# hybrid_lower_pcb3_3.net
KiCad netlist of a schematic drawn in EAGLE
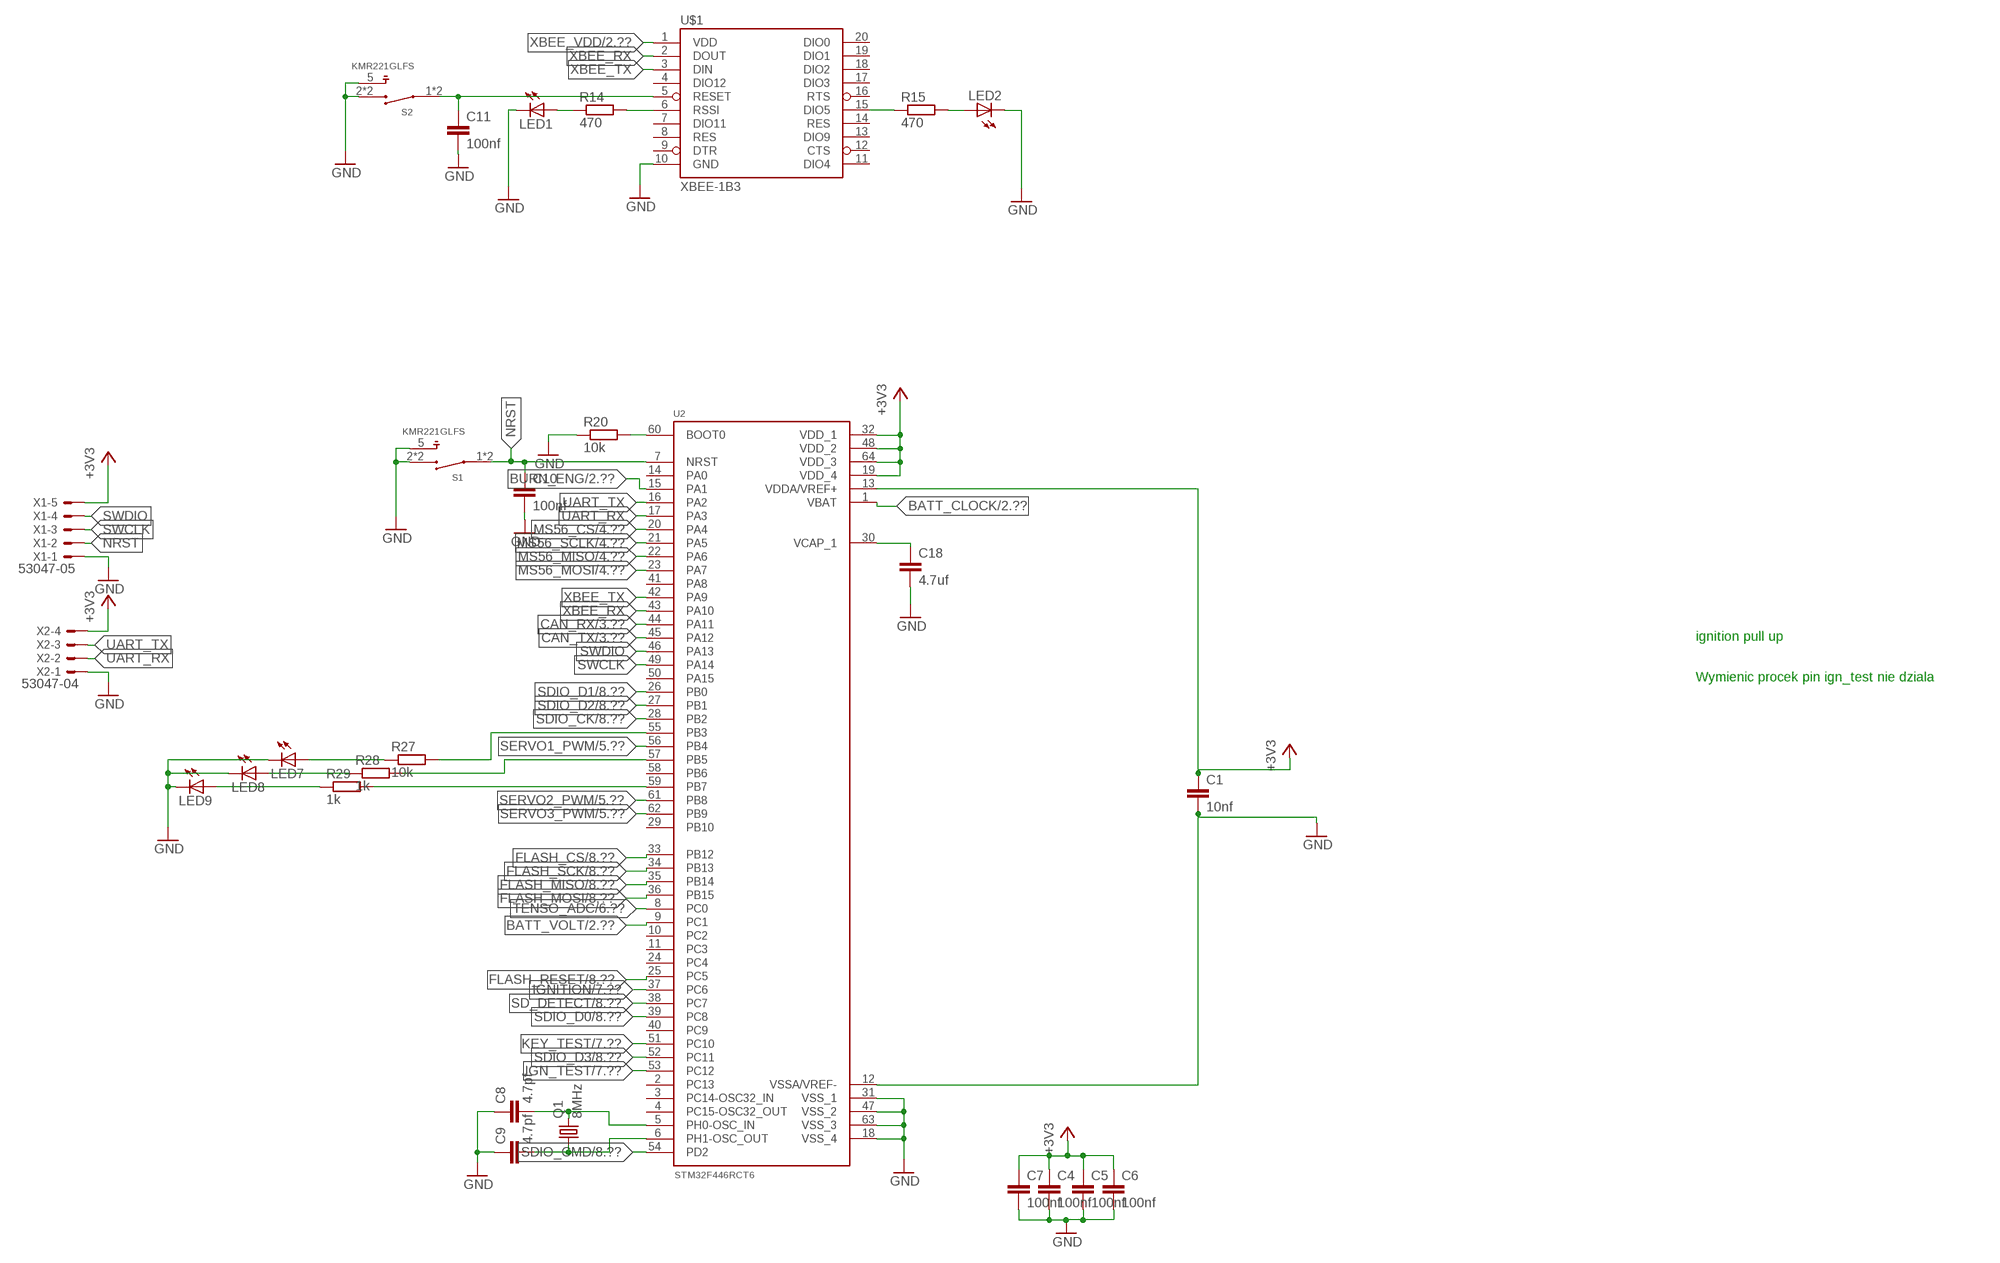
[diagram p0: schematic, sheet 1]
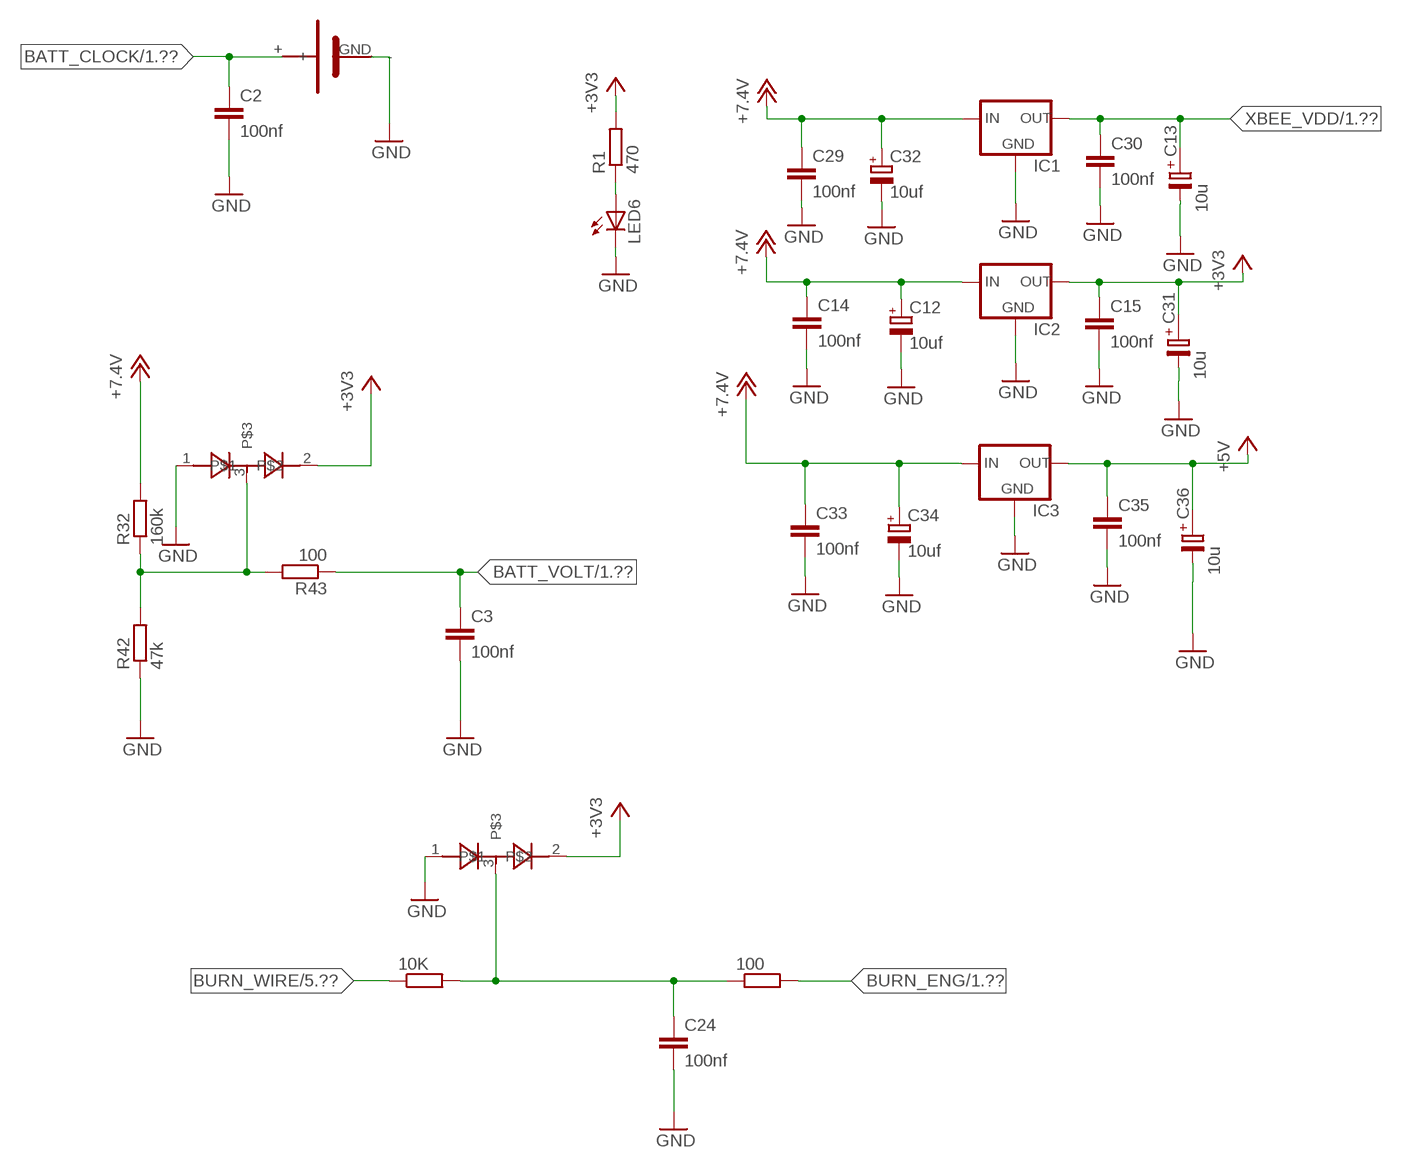
[diagram p1: schematic, sheet 2]
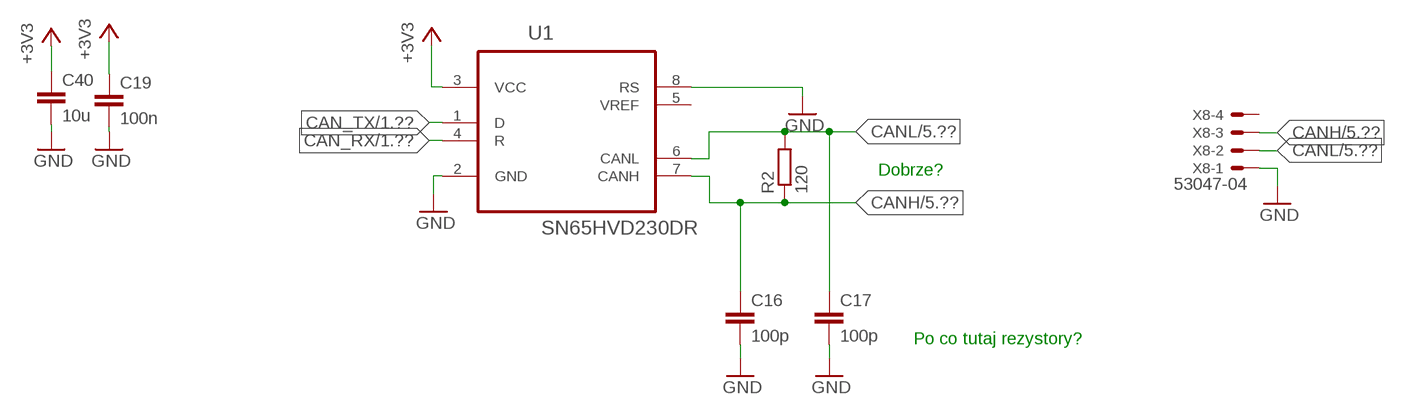
[diagram p2: schematic, sheet 3]
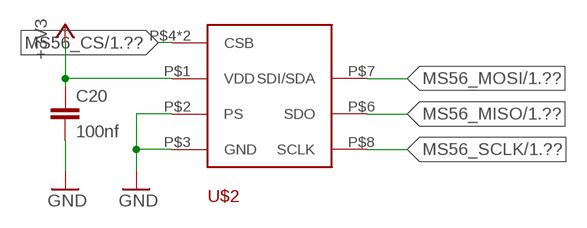
[diagram p3: schematic, sheet 4]
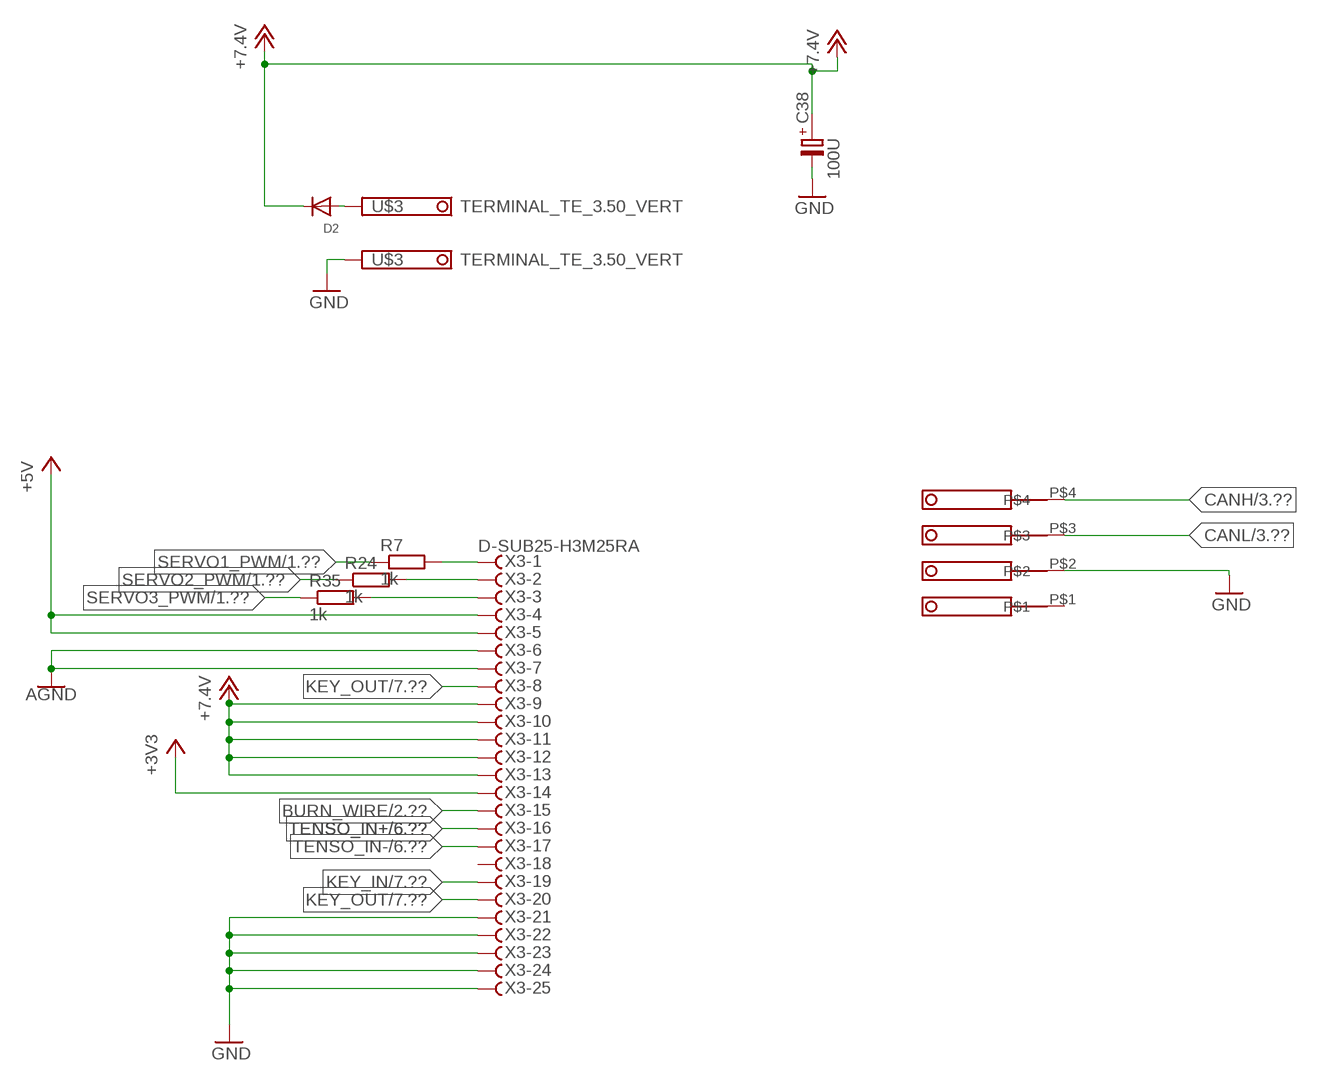
[diagram p4: schematic, sheet 5]
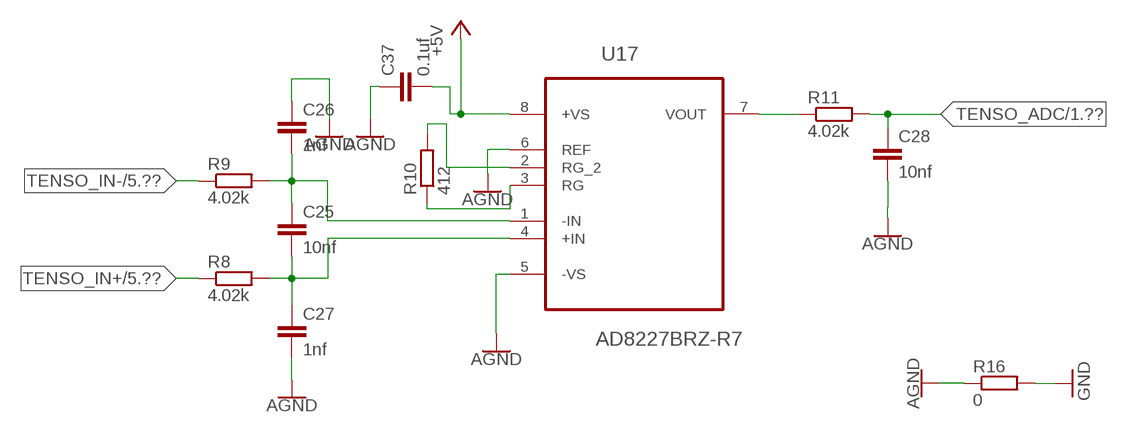
[diagram p5: schematic, sheet 6]
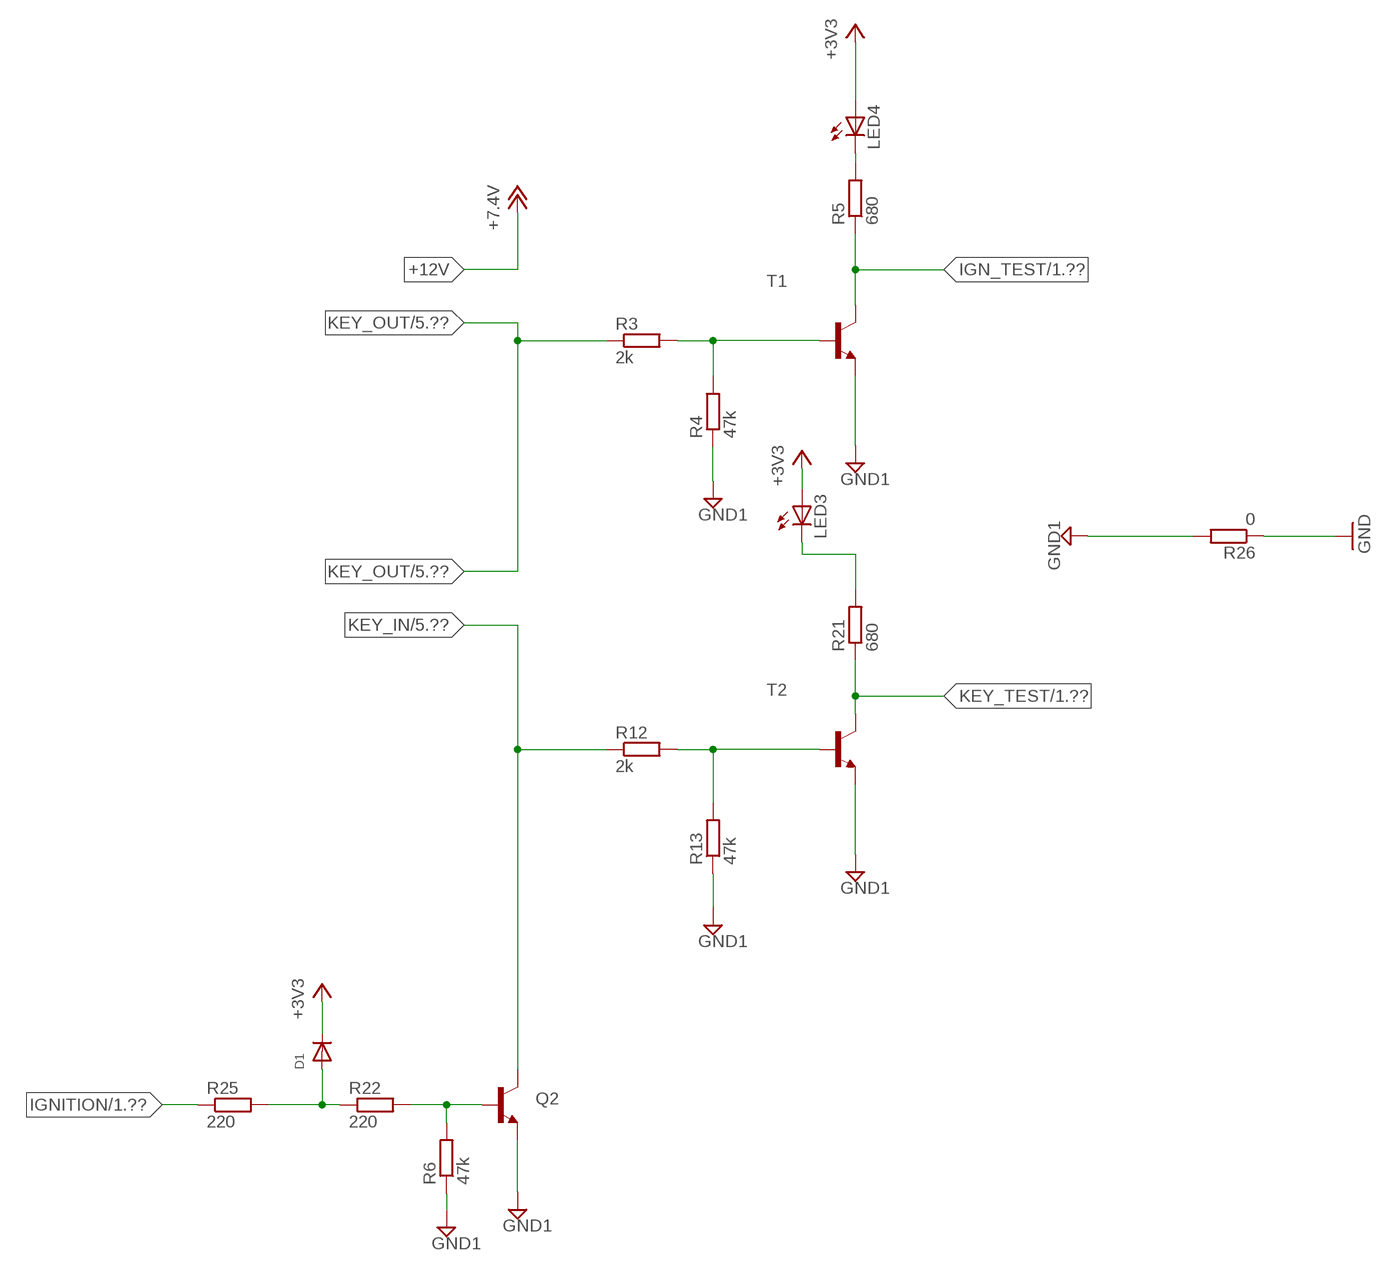
[diagram p6: schematic, sheet 7]
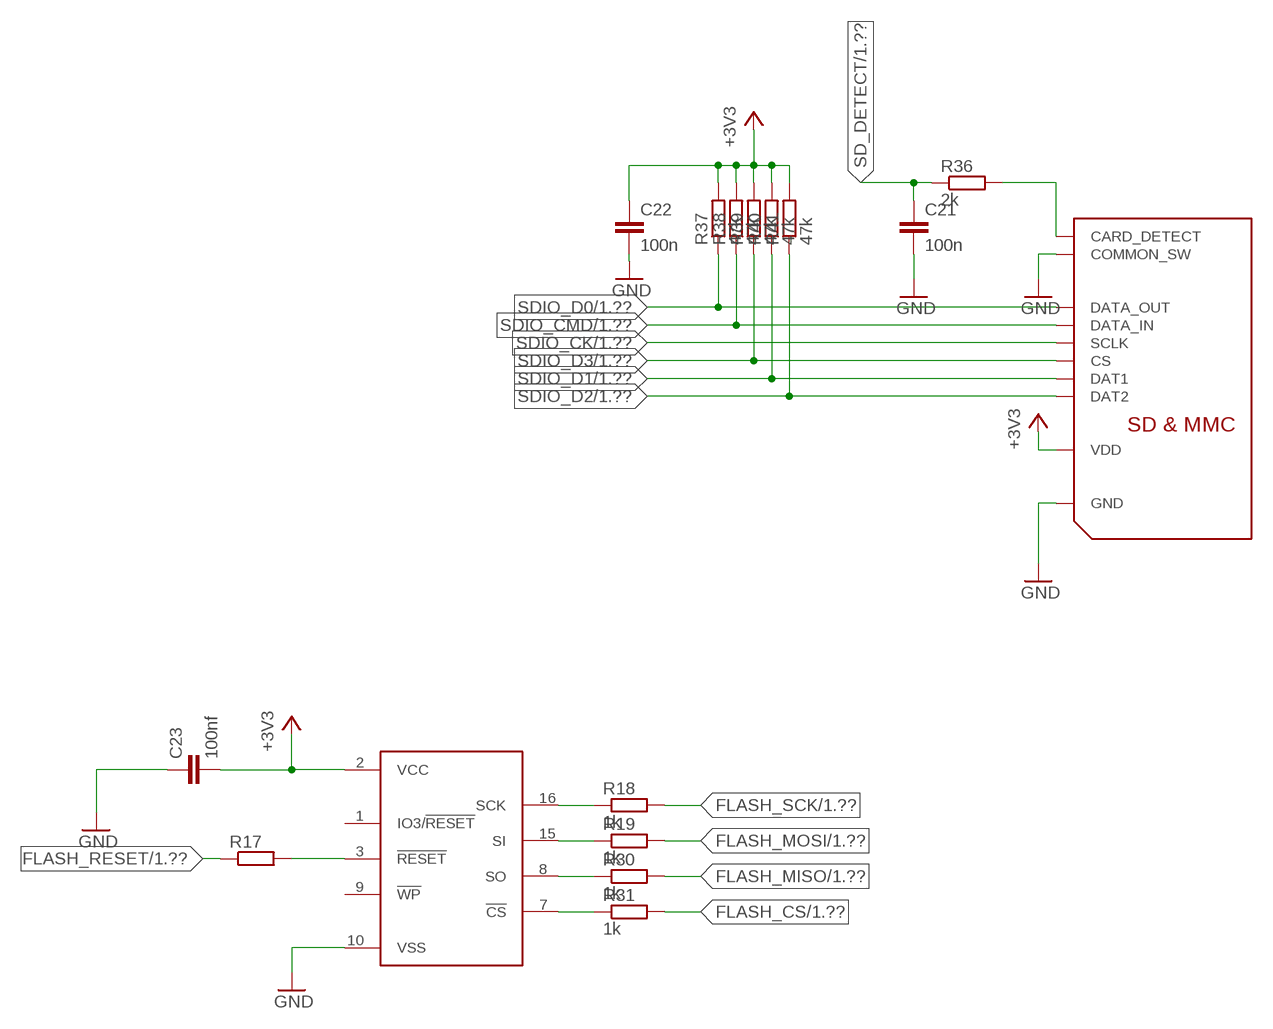
[diagram p7: schematic, sheet 8]

(export (version "E")
  (design (tool "Eeschema 10.0.6"))
  (components
    (comp (ref "C20")
      (value "100nf")
      (footprint "eagle-import:C0603")
      (libsource (lib "eagle-import") (part "resistor_C-EUC0603"))
    )
    (comp (ref "U$2")
      (value "MS56XX")
      (footprint "eagle-import:MS56XX")
      (libsource (lib "eagle-import") (part "MS56XX"))
    )
    (comp (ref "C1")
      (value "10nf")
      (footprint "eagle-import:C0603")
      (libsource (lib "eagle-import") (part "C-EUC0603"))
    )
    (comp (ref "C4")
      (value "100nf")
      (footprint "eagle-import:C0603")
      (libsource (lib "eagle-import") (part "C-EUC0603"))
    )
    (comp (ref "C5")
      (value "100nf")
      (footprint "eagle-import:C0603")
      (libsource (lib "eagle-import") (part "C-EUC0603"))
    )
    (comp (ref "C6")
      (value "100nf")
      (footprint "eagle-import:C0603")
      (libsource (lib "eagle-import") (part "C-EUC0603"))
    )
    (comp (ref "C7")
      (value "100nf")
      (footprint "eagle-import:C0603")
      (libsource (lib "eagle-import") (part "C-EUC0603"))
    )
    (comp (ref "C8")
      (value "4.7pf")
      (footprint "eagle-import:C0603")
      (libsource (lib "eagle-import") (part "C-EUC0603"))
    )
    (comp (ref "C9")
      (value "4.7pf")
      (footprint "eagle-import:C0603")
      (libsource (lib "eagle-import") (part "C-EUC0603"))
    )
    (comp (ref "C10")
      (value "100nf")
      (footprint "eagle-import:C0603")
      (libsource (lib "eagle-import") (part "C-EUC0603"))
    )
    (comp (ref "C11")
      (value "100nf")
      (footprint "eagle-import:C0603")
      (libsource (lib "eagle-import") (part "C-EUC0603"))
    )
    (comp (ref "C18")
      (value "4.7uf")
      (footprint "eagle-import:C0805")
      (libsource (lib "eagle-import") (part "rcl_334_C-EUC0805"))
    )
    (comp (ref "LED1")
      (value "LED0603")
      (footprint "eagle-import:LED-0603")
      (libsource (lib "eagle-import") (part "LED0603"))
    )
    (comp (ref "LED2")
      (value "LED0603")
      (footprint "eagle-import:LED-0603")
      (libsource (lib "eagle-import") (part "LED0603"))
    )
    (comp (ref "LED7")
      (value "LED0603")
      (footprint "eagle-import:LED-0603")
      (libsource (lib "eagle-import") (part "LED0603"))
    )
    (comp (ref "LED8")
      (value "LED0603")
      (footprint "eagle-import:LED-0603")
      (libsource (lib "eagle-import") (part "LED0603"))
    )
    (comp (ref "LED9")
      (value "LED0603")
      (footprint "eagle-import:LED-0603")
      (libsource (lib "eagle-import") (part "LED0603"))
    )
    (comp (ref "Q1")
      (value "8MHz")
      (footprint "eagle-import:CTS406")
      (libsource (lib "eagle-import") (part "CRYSTALCTS406"))
    )
    (comp (ref "R14")
      (value "470")
      (footprint "eagle-import:R0603")
      (libsource (lib "eagle-import") (part "R-EU_R0603"))
    )
    (comp (ref "R15")
      (value "470")
      (footprint "eagle-import:R0603")
      (libsource (lib "eagle-import") (part "R-EU_R0603"))
    )
    (comp (ref "R20")
      (value "10k")
      (footprint "eagle-import:R0603")
      (libsource (lib "eagle-import") (part "resistor_R-EU_R0603"))
    )
    (comp (ref "R27")
      (value "10k")
      (footprint "eagle-import:R0603")
      (libsource (lib "eagle-import") (part "resistor_R-EU_R0603"))
    )
    (comp (ref "R28")
      (value "1k")
      (footprint "eagle-import:R0603")
      (libsource (lib "eagle-import") (part "resistor_R-EU_R0603"))
    )
    (comp (ref "R29")
      (value "1k")
      (footprint "eagle-import:R0603")
      (libsource (lib "eagle-import") (part "resistor_R-EU_R0603"))
    )
    (comp (ref "S1")
      (value "KMR221GLFS")
      (footprint "eagle-import:SW_KMR221GLFS")
      (fields (field (name "MF") "C&K Components"))
      (libsource (lib "eagle-import") (part "KMR221GLFS"))
    )
    (comp (ref "S2")
      (value "KMR221GLFS")
      (footprint "eagle-import:SW_KMR221GLFS")
      (fields (field (name "MF") "C&K Components"))
      (libsource (lib "eagle-import") (part "KMR221GLFS"))
    )
    (comp (ref "U$1")
      (value "XBEE-1B3")
      (footprint "eagle-import:XBEE-SMD")
      (libsource (lib "eagle-import") (part "XBEE-1B3"))
    )
    (comp (ref "U2")
      (value "STM32F446RCT6")
      (footprint "eagle-import:QFP50P1200X1200X160-64N")
      (fields (field (name "MF") "STMicroelectronics"))
      (libsource (lib "eagle-import") (part "STM32F446RCT6"))
    )
    (comp (ref "X1")
      (value "53047-05")
      (footprint "eagle-import:53047-05")
      (fields (field (name "MF") "MOLEX") (field (name "MPN") "53047-0510"))
      (libsource (lib "eagle-import") (part "53?-05047"))
    )
    (comp (ref "X2")
      (value "53047-04")
      (footprint "eagle-import:53047-04")
      (fields (field (name "MF") "WALDOM/MOLEX") (field (name "MPN") "53047-0410"))
      (libsource (lib "eagle-import") (part "53?-04047"))
    )
    (comp (ref "C38")
      (value "100U")
      (footprint "eagle-import:TE-B-3528")
      (libsource (lib "eagle-import") (part "C-PR-SMD-TE-B"))
    )
    (comp (ref "D2")
      (value "DIODESOD-523")
      (footprint "eagle-import:SOD-523")
      (libsource (lib "eagle-import") (part "DIODESOD-523"))
    )
    (comp (ref "R7")
      (value "1k")
      (footprint "eagle-import:R0603")
      (libsource (lib "eagle-import") (part "rcl_334_R-EU_R0603"))
    )
    (comp (ref "R24")
      (value "1k")
      (footprint "eagle-import:R0603")
      (libsource (lib "eagle-import") (part "rcl_334_R-EU_R0603"))
    )
    (comp (ref "R35")
      (value "1k")
      (footprint "eagle-import:R0603")
      (libsource (lib "eagle-import") (part "rcl_334_R-EU_R0603"))
    )
    (comp (ref "U$3")
      (value "TERMINAL_TE_3.50_VERT")
      (footprint "eagle-import:TE_3.5_TERMINAL_VERT")
      (libsource (lib "eagle-import") (part "TERMINAL_TE_3.50_VERT"))
    )
    (comp (ref "U$10")
      (value "39505-1005")
      (footprint "eagle-import:39505-1005")
      (libsource (lib "eagle-import") (part "39505-1005"))
    )
    (comp (ref "X3")
      (value "D-SUB25-H3M25RA")
      (footprint "eagle-import:H3M25RA")
      (libsource (lib "eagle-import") (part "D-SUB25-H3M25RA"))
    )
    (comp (ref "10K")
      (value "R-EU_R0603")
      (footprint "eagle-import:R0603")
      (libsource (lib "eagle-import") (part "rcl_334_R-EU_R0603"))
    )
    (comp (ref "100")
      (value "R-EU_R0603")
      (footprint "eagle-import:R0603")
      (libsource (lib "eagle-import") (part "rcl_334_R-EU_R0603"))
    )
    (comp (ref "C2")
      (value "100nf")
      (footprint "eagle-import:C0603")
      (libsource (lib "eagle-import") (part "C-EUC0603"))
    )
    (comp (ref "C3")
      (value "100nf")
      (footprint "eagle-import:C0603")
      (libsource (lib "eagle-import") (part "rcl_334_C-EUC0603"))
    )
    (comp (ref "C12")
      (value "10uf")
      (footprint "eagle-import:SANYO-OSCON_SMD_B6")
      (libsource (lib "eagle-import") (part "CPOL-EUSANYO_SMD_B6"))
    )
    (comp (ref "C13")
      (value "10u")
      (footprint "eagle-import:TE-B-3528")
      (libsource (lib "eagle-import") (part "C-PR-SMD-TE-B"))
    )
    (comp (ref "C14")
      (value "100nf")
      (footprint "eagle-import:C0603")
      (libsource (lib "eagle-import") (part "C-EUC0603"))
    )
    (comp (ref "C15")
      (value "100nf")
      (footprint "eagle-import:C0603")
      (libsource (lib "eagle-import") (part "C-EUC0603"))
    )
    (comp (ref "C24")
      (value "100nf")
      (footprint "eagle-import:C0603")
      (libsource (lib "eagle-import") (part "rcl_334_C-EUC0603"))
    )
    (comp (ref "C29")
      (value "100nf")
      (footprint "eagle-import:C0603")
      (libsource (lib "eagle-import") (part "C-EUC0603"))
    )
    (comp (ref "C30")
      (value "100nf")
      (footprint "eagle-import:C0603")
      (libsource (lib "eagle-import") (part "C-EUC0603"))
    )
    (comp (ref "C31")
      (value "10u")
      (footprint "eagle-import:TE-B-3528")
      (libsource (lib "eagle-import") (part "C-PR-SMD-TE-B"))
    )
    (comp (ref "C32")
      (value "10uf")
      (footprint "eagle-import:SANYO-OSCON_SMD_B6")
      (libsource (lib "eagle-import") (part "CPOL-EUSANYO_SMD_B6"))
    )
    (comp (ref "C33")
      (value "100nf")
      (footprint "eagle-import:C0603")
      (libsource (lib "eagle-import") (part "C-EUC0603"))
    )
    (comp (ref "C34")
      (value "10uf")
      (footprint "eagle-import:SANYO-OSCON_SMD_B6")
      (libsource (lib "eagle-import") (part "CPOL-EUSANYO_SMD_B6"))
    )
    (comp (ref "C35")
      (value "100nf")
      (footprint "eagle-import:C0603")
      (libsource (lib "eagle-import") (part "C-EUC0603"))
    )
    (comp (ref "C36")
      (value "10u")
      (footprint "eagle-import:TE-B-3528")
      (libsource (lib "eagle-import") (part "C-PR-SMD-TE-B"))
    )
    (comp (ref "IC1")
      (value "LM1117")
      (footprint "eagle-import:SOT223")
      (libsource (lib "eagle-import") (part "LM1117"))
    )
    (comp (ref "IC2")
      (value "LM1117")
      (footprint "eagle-import:SOT223")
      (libsource (lib "eagle-import") (part "LM1117"))
    )
    (comp (ref "IC3")
      (value "LM1117")
      (footprint "eagle-import:SOT223")
      (libsource (lib "eagle-import") (part "LM1117"))
    )
    (comp (ref "LED6")
      (value "LED0603")
      (footprint "eagle-import:LED-0603")
      (libsource (lib "eagle-import") (part "LED0603"))
    )
    (comp (ref "R1")
      (value "470")
      (footprint "eagle-import:R0603")
      (libsource (lib "eagle-import") (part "resistor_R-EU_R0603"))
    )
    (comp (ref "R32")
      (value "160k")
      (footprint "eagle-import:R0603")
      (libsource (lib "eagle-import") (part "rcl_334_R-EU_R0603"))
    )
    (comp (ref "R42")
      (value "47k")
      (footprint "eagle-import:R0603")
      (libsource (lib "eagle-import") (part "rcl_334_R-EU_R0603"))
    )
    (comp (ref "R43")
      (value "100")
      (footprint "eagle-import:R0603")
      (libsource (lib "eagle-import") (part "rcl_334_R-EU_R0603"))
    )
    (comp (ref "U$13")
      (value "CR1220_POZ")
      (footprint "eagle-import:CR1220_POZ")
      (libsource (lib "eagle-import") (part "CR1220_POZ"))
    )
    (comp (ref "U$17")
      (value "BAS40W-04")
      (footprint "eagle-import:SOT65P210X110-3N")
      (libsource (lib "eagle-import") (part "BAS40W-04"))
    )
    (comp (ref "U$19")
      (value "BAS40W-04")
      (footprint "eagle-import:SOT65P210X110-3N")
      (libsource (lib "eagle-import") (part "BAS40W-04"))
    )
    (comp (ref "C16")
      (value "100p")
      (footprint "eagle-import:C0603")
      (libsource (lib "eagle-import") (part "C-EUC0603"))
    )
    (comp (ref "C17")
      (value "100p")
      (footprint "eagle-import:C0603")
      (libsource (lib "eagle-import") (part "C-EUC0603"))
    )
    (comp (ref "C19")
      (value "100n")
      (footprint "eagle-import:C0603")
      (libsource (lib "eagle-import") (part "C-EUC0603"))
    )
    (comp (ref "C40")
      (value "10u")
      (footprint "eagle-import:C0805")
      (libsource (lib "eagle-import") (part "C-EUC0805"))
    )
    (comp (ref "R2")
      (value "120")
      (footprint "eagle-import:R0603")
      (libsource (lib "eagle-import") (part "R-EU_R0603"))
    )
    (comp (ref "U1")
      (value "SN65HVD230DR")
      (footprint "eagle-import:SOIC127P600X175-8N")
      (fields (field (name "MF") "Texas Instruments"))
      (libsource (lib "eagle-import") (part "SN65HVD230DR"))
    )
    (comp (ref "X8")
      (value "53047-04")
      (footprint "eagle-import:53047-04")
      (fields (field (name "MF") "WALDOM/MOLEX") (field (name "MPN") "53047-0410"))
      (libsource (lib "eagle-import") (part "53?-04047"))
    )
    (comp (ref "D1")
      (value "DIODESOD-523")
      (footprint "eagle-import:SOD-523")
      (libsource (lib "eagle-import") (part "adafruit_420_DIODESOD-523"))
    )
    (comp (ref "LED3")
      (value "LED0603")
      (footprint "eagle-import:LED-0603")
      (libsource (lib "eagle-import") (part "LED0603"))
    )
    (comp (ref "LED4")
      (value "LED0603")
      (footprint "eagle-import:LED-0603")
      (libsource (lib "eagle-import") (part "LED0603"))
    )
    (comp (ref "Q2")
      (value "TRANSISTOR_NPNSOT23-3")
      (footprint "eagle-import:SOT23-3")
      (libsource (lib "eagle-import") (part "TRANSISTOR_NPNSOT23-3"))
    )
    (comp (ref "R3")
      (value "2k")
      (footprint "eagle-import:R0603")
      (libsource (lib "eagle-import") (part "R-EU_R0603"))
    )
    (comp (ref "R4")
      (value "47k")
      (footprint "eagle-import:R0603")
      (libsource (lib "eagle-import") (part "R-EU_R0603"))
    )
    (comp (ref "R5")
      (value "680")
      (footprint "eagle-import:R0603")
      (libsource (lib "eagle-import") (part "R-EU_R0603"))
    )
    (comp (ref "R6")
      (value "47k")
      (footprint "eagle-import:R0603")
      (libsource (lib "eagle-import") (part "R-EU_R0603"))
    )
    (comp (ref "R12")
      (value "2k")
      (footprint "eagle-import:R0603")
      (libsource (lib "eagle-import") (part "R-EU_R0603"))
    )
    (comp (ref "R13")
      (value "47k")
      (footprint "eagle-import:R0603")
      (libsource (lib "eagle-import") (part "R-EU_R0603"))
    )
    (comp (ref "R21")
      (value "680")
      (footprint "eagle-import:R0603")
      (libsource (lib "eagle-import") (part "R-EU_R0603"))
    )
    (comp (ref "R22")
      (value "220")
      (footprint "eagle-import:R0603")
      (libsource (lib "eagle-import") (part "R-EU_R0603"))
    )
    (comp (ref "R25")
      (value "220")
      (footprint "eagle-import:R0603")
      (libsource (lib "eagle-import") (part "R-EU_R0603"))
    )
    (comp (ref "R26")
      (value "0")
      (footprint "eagle-import:R0603")
      (libsource (lib "eagle-import") (part "R-EU_R0603"))
    )
    (comp (ref "T1")
      (value "BCW81-NPN-SOT23-BEC")
      (footprint "eagle-import:SOT23-BEC")
      (libsource (lib "eagle-import") (part "-NPN-SOT23-BECBCW81"))
    )
    (comp (ref "T2")
      (value "BCW81-NPN-SOT23-BEC")
      (footprint "eagle-import:SOT23-BEC")
      (libsource (lib "eagle-import") (part "-NPN-SOT23-BECBCW81"))
    )
    (comp (ref "C25")
      (value "10nf")
      (footprint "eagle-import:C0603")
      (libsource (lib "eagle-import") (part "C-EUC0603"))
    )
    (comp (ref "C26")
      (value "1nf")
      (footprint "eagle-import:C0603")
      (libsource (lib "eagle-import") (part "C-EUC0603"))
    )
    (comp (ref "C27")
      (value "1nf")
      (footprint "eagle-import:C0603")
      (libsource (lib "eagle-import") (part "C-EUC0603"))
    )
    (comp (ref "C28")
      (value "10nf")
      (footprint "eagle-import:C0603")
      (libsource (lib "eagle-import") (part "C-EUC0603"))
    )
    (comp (ref "C37")
      (value "0.1uf")
      (footprint "eagle-import:C0603")
      (libsource (lib "eagle-import") (part "C-EUC0603"))
    )
    (comp (ref "R8")
      (value "4.02k")
      (footprint "eagle-import:R0603")
      (libsource (lib "eagle-import") (part "R-EU_R0603"))
    )
    (comp (ref "R9")
      (value "4.02k")
      (footprint "eagle-import:R0603")
      (libsource (lib "eagle-import") (part "R-EU_R0603"))
    )
    (comp (ref "R10")
      (value "412")
      (footprint "eagle-import:R0805")
      (libsource (lib "eagle-import") (part "R-EU_R0805"))
    )
    (comp (ref "R11")
      (value "4.02k")
      (footprint "eagle-import:R0603")
      (libsource (lib "eagle-import") (part "R-EU_R0603"))
    )
    (comp (ref "R16")
      (value "0")
      (footprint "eagle-import:R0603")
      (libsource (lib "eagle-import") (part "resistor_R-EU_R0603"))
    )
    (comp (ref "U17")
      (value "AD8227BRZ-R7")
      (footprint "eagle-import:SOIC127P600X175-8N")
      (libsource (lib "eagle-import") (part "AD8227BRZ-R7"))
    )
    (comp (ref "C21")
      (value "100n")
      (footprint "eagle-import:C0603K")
      (libsource (lib "eagle-import") (part "C-EUC0603K"))
    )
    (comp (ref "C22")
      (value "100n")
      (footprint "eagle-import:C0603K")
      (libsource (lib "eagle-import") (part "C-EUC0603K"))
    )
    (comp (ref "C23")
      (value "100nf")
      (footprint "eagle-import:C0603")
      (libsource (lib "eagle-import") (part "rcl_334_C-EUC0603"))
    )
    (comp (ref "R17")
      (value "R-EU_R0603")
      (footprint "eagle-import:R0603")
      (libsource (lib "eagle-import") (part "rcl_334_R-EU_R0603"))
    )
    (comp (ref "R18")
      (value "1k")
      (footprint "eagle-import:R0603")
      (libsource (lib "eagle-import") (part "rcl_334_R-EU_R0603"))
    )
    (comp (ref "R19")
      (value "1k")
      (footprint "eagle-import:R0603")
      (libsource (lib "eagle-import") (part "rcl_334_R-EU_R0603"))
    )
    (comp (ref "R30")
      (value "1k")
      (footprint "eagle-import:R0603")
      (libsource (lib "eagle-import") (part "rcl_334_R-EU_R0603"))
    )
    (comp (ref "R31")
      (value "1k")
      (footprint "eagle-import:R0603")
      (libsource (lib "eagle-import") (part "rcl_334_R-EU_R0603"))
    )
    (comp (ref "R36")
      (value "2k")
      (footprint "eagle-import:R0603")
      (libsource (lib "eagle-import") (part "R-EU_R0603"))
    )
    (comp (ref "R37")
      (value "47k")
      (footprint "eagle-import:R0603")
      (libsource (lib "eagle-import") (part "R-EU_R0603"))
    )
    (comp (ref "R38")
      (value "47k")
      (footprint "eagle-import:R0603")
      (libsource (lib "eagle-import") (part "R-EU_R0603"))
    )
    (comp (ref "R39")
      (value "47k")
      (footprint "eagle-import:R0603")
      (libsource (lib "eagle-import") (part "R-EU_R0603"))
    )
    (comp (ref "R40")
      (value "47k")
      (footprint "eagle-import:R0603")
      (libsource (lib "eagle-import") (part "R-EU_R0603"))
    )
    (comp (ref "R41")
      (value "47k")
      (footprint "eagle-import:R0603")
      (libsource (lib "eagle-import") (part "R-EU_R0603"))
    )
    (comp (ref "U$11")
      (value "S25FLX")
      (footprint "eagle-import:SOIC16")
      (libsource (lib "eagle-import") (part "S25FLX"))
    )
    (comp (ref "U$16")
      (value "MOLEX_MICRO_SD_503182-1853")
      (footprint "eagle-import:MOLEX_MICRO_SD_503182-1853")
      (libsource (lib "eagle-import") (part "MOLEX_MICRO_SD_503182-1853"))
    )
  )
  (nets
    (net (code "1") (name "+3V3") (class "Default")
      (node (ref "C1") (pin "1") (pinfunction "1_1") (pintype "passive"))
      (node (ref "C15") (pin "1") (pinfunction "1_1") (pintype "passive"))
      (node (ref "C19") (pin "1") (pinfunction "1_1") (pintype "passive"))
      (node (ref "C20") (pin "1") (pinfunction "1_1") (pintype "passive"))
      (node (ref "C22") (pin "1") (pinfunction "1_1") (pintype "passive"))
      (node (ref "C23") (pin "2") (pinfunction "2_2") (pintype "passive"))
      (node (ref "C31") (pin "+") (pinfunction "+_+") (pintype "passive"))
      (node (ref "C4") (pin "1") (pinfunction "1_1") (pintype "passive"))
      (node (ref "C40") (pin "1") (pinfunction "1_1") (pintype "passive"))
      (node (ref "C5") (pin "1") (pinfunction "1_1") (pintype "passive"))
      (node (ref "C6") (pin "1") (pinfunction "1_1") (pintype "passive"))
      (node (ref "C7") (pin "1") (pinfunction "1_1") (pintype "passive"))
      (node (ref "D1") (pin "K") (pinfunction "C_K") (pintype "passive"))
      (node (ref "IC2") (pin "2") (pinfunction "OUT_2") (pintype "passive"))
      (node (ref "LED3") (pin "A") (pinfunction "A_A") (pintype "passive"))
      (node (ref "LED4") (pin "A") (pinfunction "A_A") (pintype "passive"))
      (node (ref "R1") (pin "2") (pinfunction "2_2") (pintype "passive"))
      (node (ref "R37") (pin "2") (pinfunction "2_2") (pintype "passive"))
      (node (ref "R38") (pin "2") (pinfunction "2_2") (pintype "passive"))
      (node (ref "R39") (pin "2") (pinfunction "2_2") (pintype "passive"))
      (node (ref "R40") (pin "2") (pinfunction "2_2") (pintype "passive"))
      (node (ref "R41") (pin "2") (pinfunction "2_2") (pintype "passive"))
      (node (ref "U$11") (pin "2") (pinfunction "VCC_2") (pintype "bidirectional"))
      (node (ref "U$16") (pin "PIN4") (pinfunction "VDD_PIN4") (pintype "power_in"))
      (node (ref "U$17") (pin "2") (pinfunction "P$2_2") (pintype "bidirectional"))
      (node (ref "U$19") (pin "2") (pinfunction "P$2_2") (pintype "bidirectional"))
      (node (ref "U$2") (pin "P$1") (pinfunction "VDD_P$1") (pintype "bidirectional"))
      (node (ref "U1") (pin "3") (pinfunction "VCC_3") (pintype "power_in"))
      (node (ref "U2") (pin "13") (pinfunction "VDDA/VREF+_13") (pintype "power_in"))
      (node (ref "U2") (pin "19") (pinfunction "VDD_4_19") (pintype "power_in"))
      (node (ref "U2") (pin "32") (pinfunction "VDD_1_32") (pintype "power_in"))
      (node (ref "U2") (pin "48") (pinfunction "VDD_2_48") (pintype "power_in"))
      (node (ref "U2") (pin "64") (pinfunction "VDD_3_64") (pintype "power_in"))
      (node (ref "X1") (pin "5") (pinfunction "S_5") (pintype "passive"))
      (node (ref "X2") (pin "4") (pinfunction "S_4") (pintype "passive"))
      (node (ref "X3") (pin "14") (pinfunction "F_14") (pintype "passive"))
    )
    (net (code "2") (name "+5V") (class "Default")
      (node (ref "C35") (pin "1") (pinfunction "1_1") (pintype "passive"))
      (node (ref "C36") (pin "+") (pinfunction "+_+") (pintype "passive"))
      (node (ref "C37") (pin "2") (pinfunction "2_2") (pintype "passive"))
      (node (ref "IC3") (pin "2") (pinfunction "OUT_2") (pintype "passive"))
      (node (ref "U17") (pin "8") (pinfunction "+VS_8") (pintype "power_in"))
      (node (ref "X3") (pin "4") (pinfunction "F_4") (pintype "passive"))
      (node (ref "X3") (pin "5") (pinfunction "F_5") (pintype "passive"))
    )
    (net (code "3") (name "+12V") (class "Default")
      (node (ref "C12") (pin "+") (pinfunction "+_+") (pintype "passive"))
      (node (ref "C14") (pin "1") (pinfunction "1_1") (pintype "passive"))
      (node (ref "C29") (pin "1") (pinfunction "1_1") (pintype "passive"))
      (node (ref "C32") (pin "+") (pinfunction "+_+") (pintype "passive"))
      (node (ref "C33") (pin "1") (pinfunction "1_1") (pintype "passive"))
      (node (ref "C34") (pin "+") (pinfunction "+_+") (pintype "passive"))
      (node (ref "C38") (pin "+") (pinfunction "+_+") (pintype "passive"))
      (node (ref "D2") (pin "K") (pinfunction "C_K") (pintype "passive"))
      (node (ref "IC1") (pin "3") (pinfunction "IN_3") (pintype "input"))
      (node (ref "IC2") (pin "3") (pinfunction "IN_3") (pintype "input"))
      (node (ref "IC3") (pin "3") (pinfunction "IN_3") (pintype "input"))
      (node (ref "R32") (pin "2") (pinfunction "2_2") (pintype "passive"))
      (node (ref "X3") (pin "10") (pinfunction "F_10") (pintype "passive"))
      (node (ref "X3") (pin "11") (pinfunction "F_11") (pintype "passive"))
      (node (ref "X3") (pin "12") (pinfunction "F_12") (pintype "passive"))
      (node (ref "X3") (pin "13") (pinfunction "F_13") (pintype "passive"))
      (node (ref "X3") (pin "9") (pinfunction "F_9") (pintype "passive"))
    )
    (net (code "4") (name "AGND") (class "Default")
      (node (ref "C26") (pin "1") (pinfunction "1_1") (pintype "passive"))
      (node (ref "C27") (pin "2") (pinfunction "2_2") (pintype "passive"))
      (node (ref "C28") (pin "2") (pinfunction "2_2") (pintype "passive"))
      (node (ref "C37") (pin "1") (pinfunction "1_1") (pintype "passive"))
      (node (ref "R16") (pin "1") (pinfunction "1_1") (pintype "passive"))
      (node (ref "U17") (pin "5") (pinfunction "-VS_5") (pintype "power_in"))
      (node (ref "U17") (pin "6") (pinfunction "REF_6") (pintype "input"))
      (node (ref "X3") (pin "6") (pinfunction "F_6") (pintype "passive"))
      (node (ref "X3") (pin "7") (pinfunction "F_7") (pintype "passive"))
    )
    (net (code "5") (name "BATT_CLOCK") (class "Default")
      (node (ref "C2") (pin "1") (pinfunction "1_1") (pintype "passive"))
      (node (ref "U$13") (pin "+") (pinfunction "+_+") (pintype "bidirectional"))
      (node (ref "U2") (pin "1") (pinfunction "VBAT_1") (pintype "power_in"))
    )
    (net (code "6") (name "BATT_VOLT") (class "Default")
      (node (ref "C3") (pin "1") (pinfunction "1_1") (pintype "passive"))
      (node (ref "R43") (pin "1") (pinfunction "1_1") (pintype "passive"))
      (node (ref "U2") (pin "9") (pinfunction "PC1_9") (pintype "bidirectional"))
    )
    (net (code "7") (name "BURN_ENG") (class "Default")
      (node (ref "100") (pin "2") (pinfunction "2_2") (pintype "passive"))
      (node (ref "U2") (pin "15") (pinfunction "PA1_15") (pintype "bidirectional"))
    )
    (net (code "8") (name "BURN_WIRE") (class "Default")
      (node (ref "10K") (pin "1") (pinfunction "1_1") (pintype "passive"))
      (node (ref "X3") (pin "15") (pinfunction "F_15") (pintype "passive"))
    )
    (net (code "9") (name "CANH") (class "Default")
      (node (ref "C16") (pin "1") (pinfunction "1_1") (pintype "passive"))
      (node (ref "R2") (pin "1") (pinfunction "1_1") (pintype "passive"))
      (node (ref "U$10") (pin "P$4") (pinfunction "P$4_P$4") (pintype "bidirectional"))
      (node (ref "U1") (pin "7") (pinfunction "CANH_7") (pintype "output"))
      (node (ref "X8") (pin "3") (pinfunction "S_3") (pintype "passive"))
    )
    (net (code "10") (name "CANL") (class "Default")
      (node (ref "C17") (pin "1") (pinfunction "1_1") (pintype "passive"))
      (node (ref "R2") (pin "2") (pinfunction "2_2") (pintype "passive"))
      (node (ref "U$10") (pin "P$3") (pinfunction "P$3_P$3") (pintype "bidirectional"))
      (node (ref "U1") (pin "6") (pinfunction "CANL_6") (pintype "output"))
      (node (ref "X8") (pin "2") (pinfunction "S_2") (pintype "passive"))
    )
    (net (code "11") (name "CAN_RX") (class "Default")
      (node (ref "U1") (pin "4") (pinfunction "R_4") (pintype "output"))
      (node (ref "U2") (pin "44") (pinfunction "PA11_44") (pintype "bidirectional"))
    )
    (net (code "12") (name "CAN_TX") (class "Default")
      (node (ref "U1") (pin "1") (pinfunction "D_1") (pintype "input"))
      (node (ref "U2") (pin "45") (pinfunction "PA12_45") (pintype "bidirectional"))
    )
    (net (code "13") (name "FLASH_CS") (class "Default")
      (node (ref "R31") (pin "2") (pinfunction "2_2") (pintype "passive"))
      (node (ref "U2") (pin "33") (pinfunction "PB12_33") (pintype "bidirectional"))
    )
    (net (code "14") (name "FLASH_MISO") (class "Default")
      (node (ref "R30") (pin "2") (pinfunction "2_2") (pintype "passive"))
      (node (ref "U2") (pin "35") (pinfunction "PB14_35") (pintype "bidirectional"))
    )
    (net (code "15") (name "FLASH_MOSI") (class "Default")
      (node (ref "R19") (pin "2") (pinfunction "2_2") (pintype "passive"))
      (node (ref "U2") (pin "36") (pinfunction "PB15_36") (pintype "bidirectional"))
    )
    (net (code "16") (name "FLASH_RESET") (class "Default")
      (node (ref "R17") (pin "1") (pinfunction "1_1") (pintype "passive"))
      (node (ref "U2") (pin "25") (pinfunction "PC5_25") (pintype "bidirectional"))
    )
    (net (code "17") (name "FLASH_SCK") (class "Default")
      (node (ref "R18") (pin "2") (pinfunction "2_2") (pintype "passive"))
      (node (ref "U2") (pin "34") (pinfunction "PB13_34") (pintype "bidirectional"))
    )
    (net (code "18") (name "GND") (class "Default")
      (node (ref "C1") (pin "2") (pinfunction "2_2") (pintype "passive"))
      (node (ref "C10") (pin "2") (pinfunction "2_2") (pintype "passive"))
      (node (ref "C11") (pin "2") (pinfunction "2_2") (pintype "passive"))
      (node (ref "C12") (pin "-") (pinfunction "-_-") (pintype "passive"))
      (node (ref "C13") (pin "-") (pinfunction "-_-") (pintype "passive"))
      (node (ref "C14") (pin "2") (pinfunction "2_2") (pintype "passive"))
      (node (ref "C15") (pin "2") (pinfunction "2_2") (pintype "passive"))
      (node (ref "C16") (pin "2") (pinfunction "2_2") (pintype "passive"))
      (node (ref "C17") (pin "2") (pinfunction "2_2") (pintype "passive"))
      (node (ref "C18") (pin "2") (pinfunction "2_2") (pintype "passive"))
      (node (ref "C19") (pin "2") (pinfunction "2_2") (pintype "passive"))
      (node (ref "C2") (pin "2") (pinfunction "2_2") (pintype "passive"))
      (node (ref "C20") (pin "2") (pinfunction "2_2") (pintype "passive"))
      (node (ref "C21") (pin "2") (pinfunction "2_2") (pintype "passive"))
      (node (ref "C22") (pin "2") (pinfunction "2_2") (pintype "passive"))
      (node (ref "C23") (pin "1") (pinfunction "1_1") (pintype "passive"))
      (node (ref "C24") (pin "2") (pinfunction "2_2") (pintype "passive"))
      (node (ref "C29") (pin "2") (pinfunction "2_2") (pintype "passive"))
      (node (ref "C3") (pin "2") (pinfunction "2_2") (pintype "passive"))
      (node (ref "C30") (pin "2") (pinfunction "2_2") (pintype "passive"))
      (node (ref "C31") (pin "-") (pinfunction "-_-") (pintype "passive"))
      (node (ref "C32") (pin "-") (pinfunction "-_-") (pintype "passive"))
      (node (ref "C33") (pin "2") (pinfunction "2_2") (pintype "passive"))
      (node (ref "C34") (pin "-") (pinfunction "-_-") (pintype "passive"))
      (node (ref "C35") (pin "2") (pinfunction "2_2") (pintype "passive"))
      (node (ref "C36") (pin "-") (pinfunction "-_-") (pintype "passive"))
      (node (ref "C38") (pin "-") (pinfunction "-_-") (pintype "passive"))
      (node (ref "C4") (pin "2") (pinfunction "2_2") (pintype "passive"))
      (node (ref "C40") (pin "2") (pinfunction "2_2") (pintype "passive"))
      (node (ref "C5") (pin "2") (pinfunction "2_2") (pintype "passive"))
      (node (ref "C6") (pin "2") (pinfunction "2_2") (pintype "passive"))
      (node (ref "C7") (pin "2") (pinfunction "2_2") (pintype "passive"))
      (node (ref "C8") (pin "1") (pinfunction "1_1") (pintype "passive"))
      (node (ref "C9") (pin "1") (pinfunction "1_1") (pintype "passive"))
      (node (ref "IC1") (pin "1") (pinfunction "GND_1") (pintype "input"))
      (node (ref "IC2") (pin "1") (pinfunction "GND_1") (pintype "input"))
      (node (ref "IC3") (pin "1") (pinfunction "GND_1") (pintype "input"))
      (node (ref "LED1") (pin "C") (pinfunction "C_C") (pintype "passive"))
      (node (ref "LED2") (pin "C") (pinfunction "C_C") (pintype "passive"))
      (node (ref "LED6") (pin "C") (pinfunction "C_C") (pintype "passive"))
      (node (ref "LED7") (pin "C") (pinfunction "C_C") (pintype "passive"))
      (node (ref "LED8") (pin "C") (pinfunction "C_C") (pintype "passive"))
      (node (ref "LED9") (pin "C") (pinfunction "C_C") (pintype "passive"))
      (node (ref "R16") (pin "2") (pinfunction "2_2") (pintype "passive"))
      (node (ref "R20") (pin "1") (pinfunction "1_1") (pintype "passive"))
      (node (ref "R26") (pin "1") (pinfunction "1_1") (pintype "passive"))
      (node (ref "R42") (pin "1") (pinfunction "1_1") (pintype "passive"))
      (node (ref "S1") (pin "2") (pinfunction "3_2") (pintype "passive"))
      (node (ref "S1") (pin "3") (pinfunction "3_3") (pintype "passive"))
      (node (ref "S1") (pin "5") (pinfunction "5_5") (pintype "passive"))
      (node (ref "S2") (pin "2") (pinfunction "3_2") (pintype "passive"))
      (node (ref "S2") (pin "3") (pinfunction "3_3") (pintype "passive"))
      (node (ref "S2") (pin "5") (pinfunction "5_5") (pintype "passive"))
      (node (ref "U$1") (pin "10") (pinfunction "GND_10") (pintype "power_in"))
      (node (ref "U$10") (pin "P$2") (pinfunction "P$2_P$2") (pintype "bidirectional"))
      (node (ref "U$11") (pin "10") (pinfunction "VSS_10") (pintype "bidirectional"))
      (node (ref "U$13") (pin "GND") (pinfunction "-_GND") (pintype "bidirectional"))
      (node (ref "U$16") (pin "DETECT_GND") (pinfunction "COMMON_SW_DETECT_GND") (pintype "passive"))
      (node (ref "U$16") (pin "PIN6") (pinfunction "GND_PIN6") (pintype "power_in"))
      (node (ref "U$17") (pin "1") (pinfunction "P$1_1") (pintype "bidirectional"))
      (node (ref "U$19") (pin "1") (pinfunction "P$1_1") (pintype "bidirectional"))
      (node (ref "U$2") (pin "P$2") (pinfunction "PS_P$2") (pintype "bidirectional"))
      (node (ref "U$2") (pin "P$3") (pinfunction "GND_P$3") (pintype "bidirectional"))
      (node (ref "U$3") (pin "P$2") (pinfunction "K1_P$2") (pintype "passive"))
      (node (ref "U1") (pin "2") (pinfunction "GND_2") (pintype "passive"))
      (node (ref "U1") (pin "8") (pinfunction "RS_8") (pintype "input"))
      (node (ref "U2") (pin "12") (pinfunction "VSSA/VREF-_12") (pintype "power_in"))
      (node (ref "U2") (pin "18") (pinfunction "VSS_4_18") (pintype "power_in"))
      (node (ref "U2") (pin "31") (pinfunction "VSS_1_31") (pintype "power_in"))
      (node (ref "U2") (pin "47") (pinfunction "VSS_2_47") (pintype "power_in"))
      (node (ref "U2") (pin "63") (pinfunction "VSS_3_63") (pintype "power_in"))
      (node (ref "X1") (pin "1") (pinfunction "S_1") (pintype "passive"))
      (node (ref "X2") (pin "1") (pinfunction "S_1") (pintype "passive"))
      (node (ref "X3") (pin "21") (pinfunction "F_21") (pintype "passive"))
      (node (ref "X3") (pin "22") (pinfunction "F_22") (pintype "passive"))
      (node (ref "X3") (pin "23") (pinfunction "F_23") (pintype "passive"))
      (node (ref "X3") (pin "24") (pinfunction "F_24") (pintype "passive"))
      (node (ref "X3") (pin "25") (pinfunction "F_25") (pintype "passive"))
      (node (ref "X8") (pin "1") (pinfunction "S_1") (pintype "passive"))
    )
    (net (code "19") (name "GND1") (class "Default")
      (node (ref "Q2") (pin "2") (pinfunction "E_2") (pintype "passive"))
      (node (ref "R13") (pin "1") (pinfunction "1_1") (pintype "passive"))
      (node (ref "R26") (pin "2") (pinfunction "2_2") (pintype "passive"))
      (node (ref "R4") (pin "1") (pinfunction "1_1") (pintype "passive"))
      (node (ref "R6") (pin "1") (pinfunction "1_1") (pintype "passive"))
      (node (ref "T1") (pin "E") (pinfunction "E_E") (pintype "passive"))
      (node (ref "T2") (pin "E") (pinfunction "E_E") (pintype "passive"))
    )
    (net (code "20") (name "IGNITION") (class "Default")
      (node (ref "R25") (pin "1") (pinfunction "1_1") (pintype "passive"))
      (node (ref "U2") (pin "37") (pinfunction "PC6_37") (pintype "bidirectional"))
    )
    (net (code "21") (name "IGN_TEST") (class "Default")
      (node (ref "R5") (pin "1") (pinfunction "1_1") (pintype "passive"))
      (node (ref "T1") (pin "C") (pinfunction "C_C") (pintype "passive"))
      (node (ref "U2") (pin "53") (pinfunction "PC12_53") (pintype "bidirectional"))
    )
    (net (code "22") (name "KEY_IN") (class "Default")
      (node (ref "Q2") (pin "3") (pinfunction "C_3") (pintype "passive"))
      (node (ref "R12") (pin "1") (pinfunction "1_1") (pintype "passive"))
      (node (ref "X3") (pin "19") (pinfunction "F_19") (pintype "passive"))
    )
    (net (code "23") (name "KEY_OUT") (class "Default")
      (node (ref "R3") (pin "1") (pinfunction "1_1") (pintype "passive"))
      (node (ref "X3") (pin "20") (pinfunction "F_20") (pintype "passive"))
      (node (ref "X3") (pin "8") (pinfunction "F_8") (pintype "passive"))
    )
    (net (code "24") (name "KEY_TEST") (class "Default")
      (node (ref "R21") (pin "1") (pinfunction "1_1") (pintype "passive"))
      (node (ref "T2") (pin "C") (pinfunction "C_C") (pintype "passive"))
      (node (ref "U2") (pin "51") (pinfunction "PC10_51") (pintype "bidirectional"))
    )
    (net (code "25") (name "MS56_CS") (class "Default")
      (node (ref "U$2") (pin "P$4") (pinfunction "CSB_P$4") (pintype "bidirectional"))
      (node (ref "U$2") (pin "P$5") (pinfunction "CSB_P$5") (pintype "bidirectional"))
      (node (ref "U2") (pin "20") (pinfunction "PA4_20") (pintype "bidirectional"))
    )
    (net (code "26") (name "MS56_MISO") (class "Default")
      (node (ref "U$2") (pin "P$6") (pinfunction "SDO_P$6") (pintype "bidirectional"))
      (node (ref "U2") (pin "22") (pinfunction "PA6_22") (pintype "bidirectional"))
    )
    (net (code "27") (name "MS56_MOSI") (class "Default")
      (node (ref "U$2") (pin "P$7") (pinfunction "SDI/SDA_P$7") (pintype "bidirectional"))
      (node (ref "U2") (pin "23") (pinfunction "PA7_23") (pintype "bidirectional"))
    )
    (net (code "28") (name "MS56_SCLK") (class "Default")
      (node (ref "U$2") (pin "P$8") (pinfunction "SCLK_P$8") (pintype "bidirectional"))
      (node (ref "U2") (pin "21") (pinfunction "PA5_21") (pintype "bidirectional"))
    )
    (net (code "29") (name "NRST") (class "Default")
      (node (ref "C10") (pin "1") (pinfunction "1_1") (pintype "passive"))
      (node (ref "S1") (pin "1") (pinfunction "1_1") (pintype "passive"))
      (node (ref "S1") (pin "4") (pinfunction "1_4") (pintype "passive"))
      (node (ref "U2") (pin "7") (pinfunction "NRST_7") (pintype "bidirectional"))
      (node (ref "X1") (pin "2") (pinfunction "S_2") (pintype "passive"))
    )
    (net (code "30") (name "Net-(D1-PadA)") (class "Default")
      (node (ref "D1") (pin "A") (pinfunction "A_A") (pintype "passive"))
      (node (ref "R22") (pin "1") (pinfunction "1_1") (pintype "passive"))
      (node (ref "R25") (pin "2") (pinfunction "2_2") (pintype "passive"))
    )
    (net (code "31") (name "Net-(LED1-PadA)") (class "Default")
      (node (ref "LED1") (pin "A") (pinfunction "A_A") (pintype "passive"))
      (node (ref "R14") (pin "1") (pinfunction "1_1") (pintype "passive"))
    )
    (net (code "32") (name "Net-(LED2-PadA)") (class "Default")
      (node (ref "LED2") (pin "A") (pinfunction "A_A") (pintype "passive"))
      (node (ref "R15") (pin "2") (pinfunction "2_2") (pintype "passive"))
    )
    (net (code "33") (name "Net-(LED3-PadC)") (class "Default")
      (node (ref "LED3") (pin "C") (pinfunction "C_C") (pintype "passive"))
      (node (ref "R21") (pin "2") (pinfunction "2_2") (pintype "passive"))
    )
    (net (code "34") (name "Net-(LED4-PadC)") (class "Default")
      (node (ref "LED4") (pin "C") (pinfunction "C_C") (pintype "passive"))
      (node (ref "R5") (pin "2") (pinfunction "2_2") (pintype "passive"))
    )
    (net (code "35") (name "Net-(LED6-PadA)") (class "Default")
      (node (ref "LED6") (pin "A") (pinfunction "A_A") (pintype "passive"))
      (node (ref "R1") (pin "1") (pinfunction "1_1") (pintype "passive"))
    )
    (net (code "36") (name "Net-(LED7-PadA)") (class "Default")
      (node (ref "LED7") (pin "A") (pinfunction "A_A") (pintype "passive"))
      (node (ref "R27") (pin "1") (pinfunction "1_1") (pintype "passive"))
    )
    (net (code "37") (name "Net-(LED8-PadA)") (class "Default")
      (node (ref "LED8") (pin "A") (pinfunction "A_A") (pintype "passive"))
      (node (ref "R28") (pin "1") (pinfunction "1_1") (pintype "passive"))
    )
    (net (code "38") (name "Net-(LED9-PadA)") (class "Default")
      (node (ref "LED9") (pin "A") (pinfunction "A_A") (pintype "passive"))
      (node (ref "R29") (pin "1") (pinfunction "1_1") (pintype "passive"))
    )
    (net (code "39") (name "Net-(Q1-2)") (class "Default")
      (node (ref "C8") (pin "2") (pinfunction "2_2") (pintype "passive"))
      (node (ref "Q1") (pin "3") (pinfunction "2_3") (pintype "passive"))
      (node (ref "U2") (pin "5") (pinfunction "PH0-OSC_IN_5") (pintype "bidirectional"))
    )
    (net (code "40") (name "Net-(Q2-B)") (class "Default")
      (node (ref "Q2") (pin "1") (pinfunction "B_1") (pintype "passive"))
      (node (ref "R22") (pin "2") (pinfunction "2_2") (pintype "passive"))
      (node (ref "R6") (pin "2") (pinfunction "2_2") (pintype "passive"))
    )
    (net (code "41") (name "Net-(R3-Pad2)") (class "Default")
      (node (ref "R3") (pin "2") (pinfunction "2_2") (pintype "passive"))
      (node (ref "R4") (pin "2") (pinfunction "2_2") (pintype "passive"))
      (node (ref "T1") (pin "B") (pinfunction "B_B") (pintype "passive"))
    )
    (net (code "42") (name "Net-(R12-Pad2)") (class "Default")
      (node (ref "R12") (pin "2") (pinfunction "2_2") (pintype "passive"))
      (node (ref "R13") (pin "2") (pinfunction "2_2") (pintype "passive"))
      (node (ref "T2") (pin "B") (pinfunction "B_B") (pintype "passive"))
    )
    (net (code "43") (name "Net-(U$1-DIO5)") (class "Default")
      (node (ref "R15") (pin "1") (pinfunction "1_1") (pintype "passive"))
      (node (ref "U$1") (pin "15") (pinfunction "DIO5_15") (pintype "bidirectional"))
    )
    (net (code "44") (name "Net-(U$1-RESET)") (class "Default")
      (node (ref "C11") (pin "1") (pinfunction "1_1") (pintype "passive"))
      (node (ref "S2") (pin "1") (pinfunction "1_1") (pintype "passive"))
      (node (ref "S2") (pin "4") (pinfunction "1_4") (pintype "passive"))
      (node (ref "U$1") (pin "5") (pinfunction "RESET_5") (pintype "input"))
    )
    (net (code "45") (name "Net-(U$1-RSSI)") (class "Default")
      (node (ref "R14") (pin "2") (pinfunction "2_2") (pintype "passive"))
      (node (ref "U$1") (pin "6") (pinfunction "RSSI_6") (pintype "bidirectional"))
    )
    (net (code "46") (name "Net-(U$3-K)") (class "Default")
      (node (ref "D2") (pin "A") (pinfunction "A_A") (pintype "passive"))
      (node (ref "U$3") (pin "P$1") (pinfunction "K_P$1") (pintype "passive"))
    )
    (net (code "47") (name "Net-(U$11-SCK)") (class "Default")
      (node (ref "R18") (pin "1") (pinfunction "1_1") (pintype "passive"))
      (node (ref "U$11") (pin "16") (pinfunction "SCK_16") (pintype "bidirectional"))
    )
    (net (code "48") (name "Net-(U$11-SI)") (class "Default")
      (node (ref "R19") (pin "1") (pinfunction "1_1") (pintype "passive"))
      (node (ref "U$11") (pin "15") (pinfunction "SI_15") (pintype "bidirectional"))
    )
    (net (code "49") (name "Net-(U$11-SO)") (class "Default")
      (node (ref "R30") (pin "1") (pinfunction "1_1") (pintype "passive"))
      (node (ref "U$11") (pin "8") (pinfunction "SO_8") (pintype "bidirectional"))
    )
    (net (code "50") (name "Net-(U$11-~{CS})") (class "Default")
      (node (ref "R31") (pin "1") (pinfunction "1_1") (pintype "passive"))
      (node (ref "U$11") (pin "7") (pinfunction "~{CS}_7") (pintype "bidirectional"))
    )
    (net (code "51") (name "Net-(U$11-~{RESET})") (class "Default")
      (node (ref "R17") (pin "2") (pinfunction "2_2") (pintype "passive"))
      (node (ref "U$11") (pin "3") (pinfunction "~{RESET}_3") (pintype "bidirectional"))
    )
    (net (code "52") (name "Net-(U$16-CARD_DETECT)") (class "Default")
      (node (ref "R36") (pin "2") (pinfunction "2_2") (pintype "passive"))
      (node (ref "U$16") (pin "DETECT") (pinfunction "CARD_DETECT_DETECT") (pintype "passive"))
    )
    (net (code "53") (name "Net-(U$17-P$3)") (class "Default")
      (node (ref "R32") (pin "1") (pinfunction "1_1") (pintype "passive"))
      (node (ref "R42") (pin "2") (pinfunction "2_2") (pintype "passive"))
      (node (ref "R43") (pin "2") (pinfunction "2_2") (pintype "passive"))
      (node (ref "U$17") (pin "3") (pinfunction "P$3_3") (pintype "bidirectional"))
    )
    (net (code "54") (name "Net-(U$19-P$3)") (class "Default")
      (node (ref "100") (pin "1") (pinfunction "1_1") (pintype "passive"))
      (node (ref "10K") (pin "2") (pinfunction "2_2") (pintype "passive"))
      (node (ref "C24") (pin "1") (pinfunction "1_1") (pintype "passive"))
      (node (ref "U$19") (pin "3") (pinfunction "P$3_3") (pintype "bidirectional"))
    )
    (net (code "55") (name "Net-(U2-BOOT0)") (class "Default")
      (node (ref "R20") (pin "2") (pinfunction "2_2") (pintype "passive"))
      (node (ref "U2") (pin "60") (pinfunction "BOOT0_60") (pintype "input"))
    )
    (net (code "56") (name "Net-(U2-PB3)") (class "Default")
      (node (ref "R27") (pin "2") (pinfunction "2_2") (pintype "passive"))
      (node (ref "U2") (pin "55") (pinfunction "PB3_55") (pintype "bidirectional"))
    )
    (net (code "57") (name "Net-(U2-PB5)") (class "Default")
      (node (ref "R28") (pin "2") (pinfunction "2_2") (pintype "passive"))
      (node (ref "U2") (pin "57") (pinfunction "PB5_57") (pintype "bidirectional"))
    )
    (net (code "58") (name "Net-(U2-PB7)") (class "Default")
      (node (ref "R29") (pin "2") (pinfunction "2_2") (pintype "passive"))
      (node (ref "U2") (pin "59") (pinfunction "PB7_59") (pintype "bidirectional"))
    )
    (net (code "59") (name "Net-(U2-PH1-OSC_OUT)") (class "Default")
      (node (ref "C9") (pin "2") (pinfunction "2_2") (pintype "passive"))
      (node (ref "Q1") (pin "1") (pinfunction "1_1") (pintype "passive"))
      (node (ref "U2") (pin "6") (pinfunction "PH1-OSC_OUT_6") (pintype "bidirectional"))
    )
    (net (code "60") (name "Net-(U2-VCAP_1)") (class "Default")
      (node (ref "C18") (pin "1") (pinfunction "1_1") (pintype "passive"))
      (node (ref "U2") (pin "30") (pinfunction "VCAP_1_30") (pintype "power_in"))
    )
    (net (code "61") (name "Net-(U17-+IN)") (class "Default")
      (node (ref "C25") (pin "2") (pinfunction "2_2") (pintype "passive"))
      (node (ref "C27") (pin "1") (pinfunction "1_1") (pintype "passive"))
      (node (ref "R8") (pin "2") (pinfunction "2_2") (pintype "passive"))
      (node (ref "U17") (pin "4") (pinfunction "+IN_4") (pintype "input"))
    )
    (net (code "62") (name "Net-(U17--IN)") (class "Default")
      (node (ref "C25") (pin "1") (pinfunction "1_1") (pintype "passive"))
      (node (ref "C26") (pin "2") (pinfunction "2_2") (pintype "passive"))
      (node (ref "R9") (pin "2") (pinfunction "2_2") (pintype "passive"))
      (node (ref "U17") (pin "1") (pinfunction "-IN_1") (pintype "input"))
    )
    (net (code "63") (name "Net-(U17-RG)") (class "Default")
      (node (ref "R10") (pin "1") (pinfunction "1_1") (pintype "passive"))
      (node (ref "U17") (pin "3") (pinfunction "RG_3") (pintype "passive"))
    )
    (net (code "64") (name "Net-(U17-RG_2)") (class "Default")
      (node (ref "R10") (pin "2") (pinfunction "2_2") (pintype "passive"))
      (node (ref "U17") (pin "2") (pinfunction "RG_2_2") (pintype "passive"))
    )
    (net (code "65") (name "Net-(U17-VOUT)") (class "Default")
      (node (ref "R11") (pin "1") (pinfunction "1_1") (pintype "passive"))
      (node (ref "U17") (pin "7") (pinfunction "VOUT_7") (pintype "output"))
    )
    (net (code "66") (name "Net-(X3A-F)") (class "Default")
      (node (ref "R7") (pin "2") (pinfunction "2_2") (pintype "passive"))
      (node (ref "X3") (pin "1") (pinfunction "F_1") (pintype "passive"))
    )
    (net (code "67") (name "Net-(X3L-F)") (class "Default")
      (node (ref "R24") (pin "2") (pinfunction "2_2") (pintype "passive"))
      (node (ref "X3") (pin "2") (pinfunction "F_2") (pintype "passive"))
    )
    (net (code "68") (name "Net-(X3S-F)") (class "Default")
      (node (ref "R35") (pin "2") (pinfunction "2_2") (pintype "passive"))
      (node (ref "X3") (pin "3") (pinfunction "F_3") (pintype "passive"))
    )
    (net (code "69") (name "SDIO_CK") (class "Default")
      (node (ref "U$16") (pin "PIN5") (pinfunction "SCLK_PIN5") (pintype "input"))
      (node (ref "U2") (pin "28") (pinfunction "PB2_28") (pintype "bidirectional"))
    )
    (net (code "70") (name "SDIO_CMD") (class "Default")
      (node (ref "R38") (pin "1") (pinfunction "1_1") (pintype "passive"))
      (node (ref "U$16") (pin "PIN3") (pinfunction "DATA_IN_PIN3") (pintype "input"))
      (node (ref "U2") (pin "54") (pinfunction "PD2_54") (pintype "bidirectional"))
    )
    (net (code "71") (name "SDIO_D0") (class "Default")
      (node (ref "R37") (pin "1") (pinfunction "1_1") (pintype "passive"))
      (node (ref "U$16") (pin "PIN7") (pinfunction "DATA_OUT_PIN7") (pintype "output"))
      (node (ref "U2") (pin "39") (pinfunction "PC8_39") (pintype "bidirectional"))
    )
    (net (code "72") (name "SDIO_D1") (class "Default")
      (node (ref "R40") (pin "1") (pinfunction "1_1") (pintype "passive"))
      (node (ref "U$16") (pin "PIN8") (pinfunction "DAT1_PIN8") (pintype "bidirectional"))
      (node (ref "U2") (pin "26") (pinfunction "PB0_26") (pintype "bidirectional"))
    )
    (net (code "73") (name "SDIO_D2") (class "Default")
      (node (ref "R41") (pin "1") (pinfunction "1_1") (pintype "passive"))
      (node (ref "U$16") (pin "PIN1") (pinfunction "DAT2_PIN1") (pintype "bidirectional"))
      (node (ref "U2") (pin "27") (pinfunction "PB1_27") (pintype "bidirectional"))
    )
    (net (code "74") (name "SDIO_D3") (class "Default")
      (node (ref "R39") (pin "1") (pinfunction "1_1") (pintype "passive"))
      (node (ref "U$16") (pin "PIN2") (pinfunction "CS_PIN2") (pintype "input"))
      (node (ref "U2") (pin "52") (pinfunction "PC11_52") (pintype "bidirectional"))
    )
    (net (code "75") (name "SD_DETECT") (class "Default")
      (node (ref "C21") (pin "1") (pinfunction "1_1") (pintype "passive"))
      (node (ref "R36") (pin "1") (pinfunction "1_1") (pintype "passive"))
      (node (ref "U2") (pin "38") (pinfunction "PC7_38") (pintype "bidirectional"))
    )
    (net (code "76") (name "SERVO1_PWM") (class "Default")
      (node (ref "R7") (pin "1") (pinfunction "1_1") (pintype "passive"))
      (node (ref "U2") (pin "56") (pinfunction "PB4_56") (pintype "bidirectional"))
    )
    (net (code "77") (name "SERVO2_PWM") (class "Default")
      (node (ref "R24") (pin "1") (pinfunction "1_1") (pintype "passive"))
      (node (ref "U2") (pin "61") (pinfunction "PB8_61") (pintype "bidirectional"))
    )
    (net (code "78") (name "SERVO3_PWM") (class "Default")
      (node (ref "R35") (pin "1") (pinfunction "1_1") (pintype "passive"))
      (node (ref "U2") (pin "62") (pinfunction "PB9_62") (pintype "bidirectional"))
    )
    (net (code "79") (name "SWCLK") (class "Default")
      (node (ref "U2") (pin "49") (pinfunction "PA14_49") (pintype "bidirectional"))
      (node (ref "X1") (pin "3") (pinfunction "S_3") (pintype "passive"))
    )
    (net (code "80") (name "SWDIO") (class "Default")
      (node (ref "U2") (pin "46") (pinfunction "PA13_46") (pintype "bidirectional"))
      (node (ref "X1") (pin "4") (pinfunction "S_4") (pintype "passive"))
    )
    (net (code "81") (name "TENSO_ADC") (class "Default")
      (node (ref "C28") (pin "1") (pinfunction "1_1") (pintype "passive"))
      (node (ref "R11") (pin "2") (pinfunction "2_2") (pintype "passive"))
      (node (ref "U2") (pin "8") (pinfunction "PC0_8") (pintype "bidirectional"))
    )
    (net (code "82") (name "TENSO_IN+") (class "Default")
      (node (ref "R8") (pin "1") (pinfunction "1_1") (pintype "passive"))
      (node (ref "X3") (pin "16") (pinfunction "F_16") (pintype "passive"))
    )
    (net (code "83") (name "TENSO_IN-") (class "Default")
      (node (ref "R9") (pin "1") (pinfunction "1_1") (pintype "passive"))
      (node (ref "X3") (pin "17") (pinfunction "F_17") (pintype "passive"))
    )
    (net (code "84") (name "UART_RX") (class "Default")
      (node (ref "U2") (pin "17") (pinfunction "PA3_17") (pintype "bidirectional"))
      (node (ref "X2") (pin "2") (pinfunction "S_2") (pintype "passive"))
    )
    (net (code "85") (name "UART_TX") (class "Default")
      (node (ref "U2") (pin "16") (pinfunction "PA2_16") (pintype "bidirectional"))
      (node (ref "X2") (pin "3") (pinfunction "S_3") (pintype "passive"))
    )
    (net (code "86") (name "XBEE_RX") (class "Default")
      (node (ref "U$1") (pin "2") (pinfunction "DOUT_2") (pintype "output"))
      (node (ref "U2") (pin "43") (pinfunction "PA10_43") (pintype "bidirectional"))
    )
    (net (code "87") (name "XBEE_TX") (class "Default")
      (node (ref "U$1") (pin "3") (pinfunction "DIN_3") (pintype "input"))
      (node (ref "U2") (pin "42") (pinfunction "PA9_42") (pintype "bidirectional"))
    )
    (net (code "88") (name "XBEE_VDD") (class "Default")
      (node (ref "C13") (pin "+") (pinfunction "+_+") (pintype "passive"))
      (node (ref "C30") (pin "1") (pinfunction "1_1") (pintype "passive"))
      (node (ref "IC1") (pin "2") (pinfunction "OUT_2") (pintype "passive"))
      (node (ref "U$1") (pin "1") (pinfunction "VDD_1") (pintype "power_in"))
    )
    (net (code "89") (name "unconnected-(U$1-CTS-Pad12)") (class "Default")
      (node (ref "U$1") (pin "12") (pinfunction "CTS_12") (pintype "output"))
    )
    (net (code "90") (name "unconnected-(U$1-DIO0-Pad20)") (class "Default")
      (node (ref "U$1") (pin "20") (pinfunction "DIO0_20") (pintype "bidirectional"))
    )
    (net (code "91") (name "unconnected-(U$1-DIO1-Pad19)") (class "Default")
      (node (ref "U$1") (pin "19") (pinfunction "DIO1_19") (pintype "bidirectional"))
    )
    (net (code "92") (name "unconnected-(U$1-DIO2-Pad18)") (class "Default")
      (node (ref "U$1") (pin "18") (pinfunction "DIO2_18") (pintype "bidirectional"))
    )
    (net (code "93") (name "unconnected-(U$1-DIO3-Pad17)") (class "Default")
      (node (ref "U$1") (pin "17") (pinfunction "DIO3_17") (pintype "bidirectional"))
    )
    (net (code "94") (name "unconnected-(U$1-DIO4-Pad11)") (class "Default")
      (node (ref "U$1") (pin "11") (pinfunction "DIO4_11") (pintype "bidirectional"))
    )
    (net (code "95") (name "unconnected-(U$1-DIO9-Pad13)") (class "Default")
      (node (ref "U$1") (pin "13") (pinfunction "DIO9_13") (pintype "bidirectional"))
    )
    (net (code "96") (name "unconnected-(U$1-DIO11-Pad7)") (class "Default")
      (node (ref "U$1") (pin "7") (pinfunction "DIO11_7") (pintype "bidirectional"))
    )
    (net (code "97") (name "unconnected-(U$1-DIO12-Pad4)") (class "Default")
      (node (ref "U$1") (pin "4") (pinfunction "DIO12_4") (pintype "bidirectional"))
    )
    (net (code "98") (name "unconnected-(U$1-DTR-Pad9)") (class "Default")
      (node (ref "U$1") (pin "9") (pinfunction "DTR_9") (pintype "bidirectional"))
    )
    (net (code "99") (name "unconnected-(U$1-RES-Pad8)") (class "Default")
      (node (ref "U$1") (pin "8") (pinfunction "RES_8") (pintype "bidirectional"))
    )
    (net (code "100") (name "unconnected-(U$1-RES-Pad14)") (class "Default")
      (node (ref "U$1") (pin "14") (pinfunction "RES_14") (pintype "bidirectional"))
    )
    (net (code "101") (name "unconnected-(U$1-RTS-Pad16)") (class "Default")
      (node (ref "U$1") (pin "16") (pinfunction "RTS_16") (pintype "input"))
    )
    (net (code "102") (name "unconnected-(U$10-PadP$1)") (class "Default")
      (node (ref "U$10") (pin "P$1") (pinfunction "P$1_P$1") (pintype "bidirectional"))
    )
    (net (code "103") (name "unconnected-(U$11-IO3{slash}~{RESET}-Pad1)") (class "Default")
      (node (ref "U$11") (pin "1") (pinfunction "IO3/~{RESET}_1") (pintype "bidirectional"))
    )
    (net (code "104") (name "unconnected-(U$11-~{WP}-Pad9)") (class "Default")
      (node (ref "U$11") (pin "9") (pinfunction "~{WP}_9") (pintype "bidirectional"))
    )
    (net (code "105") (name "unconnected-(U1-VREF-Pad5)") (class "Default")
      (node (ref "U1") (pin "5") (pinfunction "VREF_5") (pintype "output"))
    )
    (net (code "106") (name "unconnected-(U2-PA0-Pad14)") (class "Default")
      (node (ref "U2") (pin "14") (pinfunction "PA0_14") (pintype "bidirectional"))
    )
    (net (code "107") (name "unconnected-(U2-PA8-Pad41)") (class "Default")
      (node (ref "U2") (pin "41") (pinfunction "PA8_41") (pintype "bidirectional"))
    )
    (net (code "108") (name "unconnected-(U2-PA15-Pad50)") (class "Default")
      (node (ref "U2") (pin "50") (pinfunction "PA15_50") (pintype "bidirectional"))
    )
    (net (code "109") (name "unconnected-(U2-PB6-Pad58)") (class "Default")
      (node (ref "U2") (pin "58") (pinfunction "PB6_58") (pintype "bidirectional"))
    )
    (net (code "110") (name "unconnected-(U2-PB10-Pad29)") (class "Default")
      (node (ref "U2") (pin "29") (pinfunction "PB10_29") (pintype "bidirectional"))
    )
    (net (code "111") (name "unconnected-(U2-PC2-Pad10)") (class "Default")
      (node (ref "U2") (pin "10") (pinfunction "PC2_10") (pintype "bidirectional"))
    )
    (net (code "112") (name "unconnected-(U2-PC3-Pad11)") (class "Default")
      (node (ref "U2") (pin "11") (pinfunction "PC3_11") (pintype "bidirectional"))
    )
    (net (code "113") (name "unconnected-(U2-PC4-Pad24)") (class "Default")
      (node (ref "U2") (pin "24") (pinfunction "PC4_24") (pintype "bidirectional"))
    )
    (net (code "114") (name "unconnected-(U2-PC9-Pad40)") (class "Default")
      (node (ref "U2") (pin "40") (pinfunction "PC9_40") (pintype "bidirectional"))
    )
    (net (code "115") (name "unconnected-(U2-PC13-Pad2)") (class "Default")
      (node (ref "U2") (pin "2") (pinfunction "PC13_2") (pintype "bidirectional"))
    )
    (net (code "116") (name "unconnected-(U2-PC14-OSC32_IN-Pad3)") (class "Default")
      (node (ref "U2") (pin "3") (pinfunction "PC14-OSC32_IN_3") (pintype "bidirectional"))
    )
    (net (code "117") (name "unconnected-(U2-PC15-OSC32_OUT-Pad4)") (class "Default")
      (node (ref "U2") (pin "4") (pinfunction "PC15-OSC32_OUT_4") (pintype "bidirectional"))
    )
    (net (code "118") (name "unconnected-(X3J-F-Pad18)") (class "Default")
      (node (ref "X3") (pin "18") (pinfunction "F_18") (pintype "passive"))
    )
    (net (code "119") (name "unconnected-(X8D-S-Pad4)") (class "Default")
      (node (ref "X8") (pin "4") (pinfunction "S_4") (pintype "passive"))
    )
  )
)
